# ESP32_Touch_Indoor_Environment_Expansion.net
KiCad netlist of a schematic drawn in EAGLE
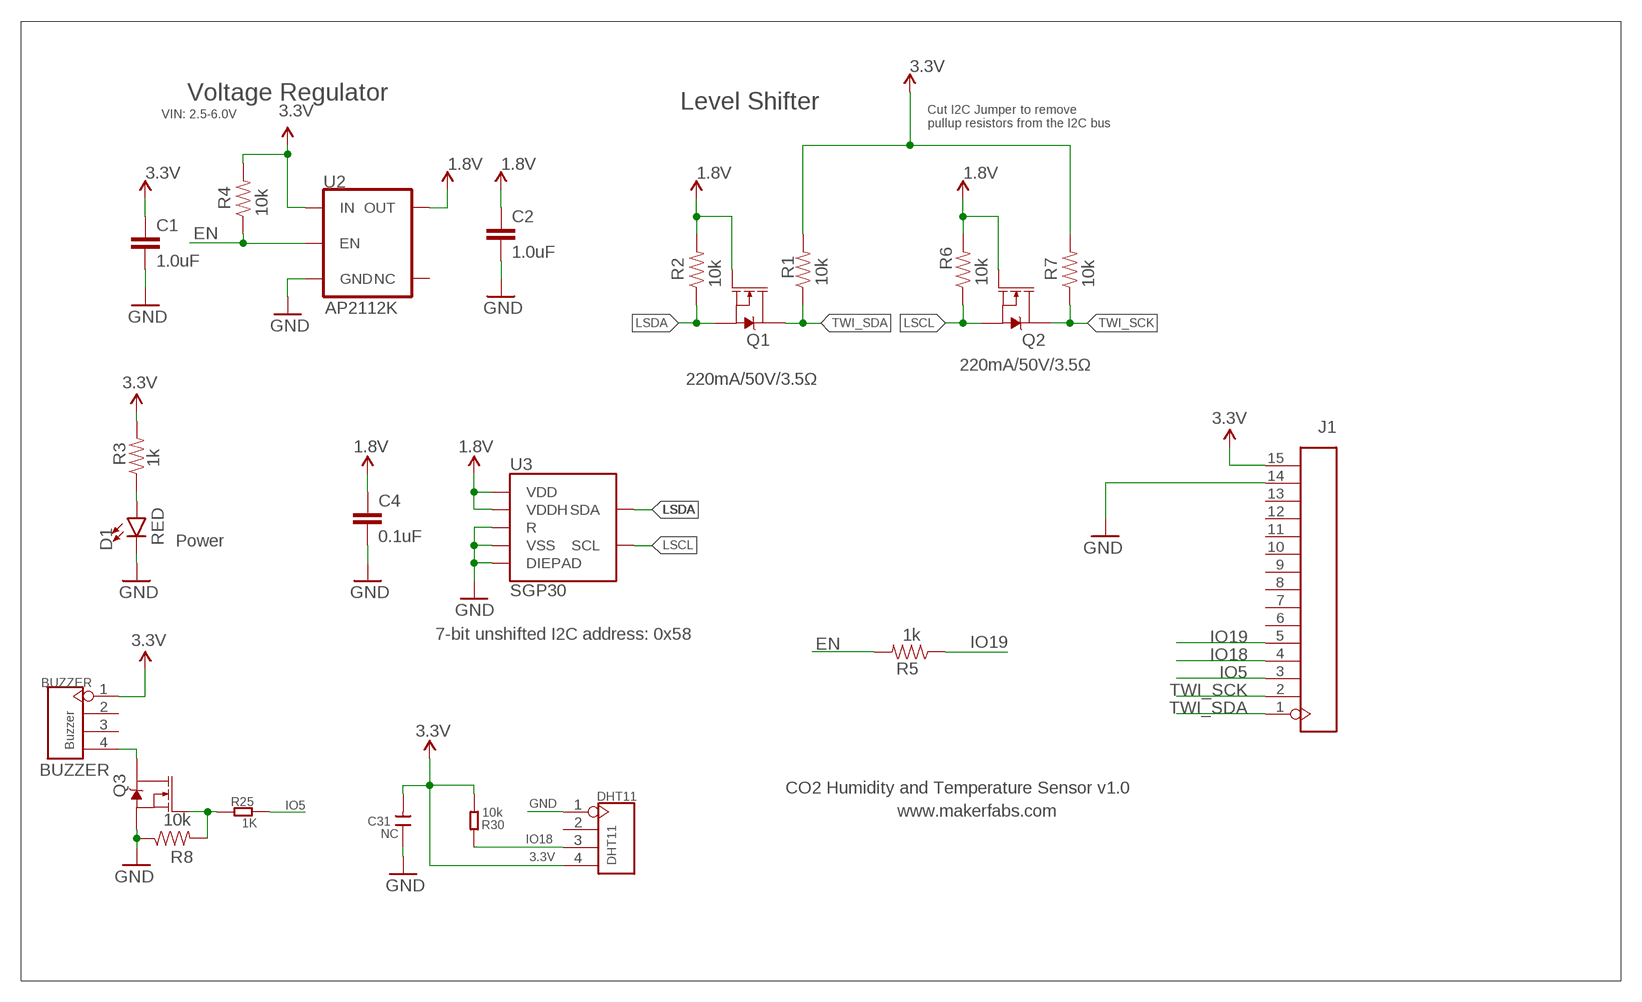
[diagram p0: schematic, sheet 1]

(export (version "E")
  (design (tool "Eeschema 10.0.6"))
  (components
    (comp (ref "BUZZER")
      (value "Buzzer")
      (footprint "eagle-import:4P-65_35ROUND")
      (libsource (lib "eagle-import") (part "HEADER-4P-60/35MILROUND"))
    )
    (comp (ref "C1")
      (value "1.0uF")
      (footprint "eagle-import:0603")
      (libsource (lib "eagle-import") (part "1.0UF-0603-16V-10%"))
    )
    (comp (ref "C2")
      (value "1.0uF")
      (footprint "eagle-import:0603")
      (libsource (lib "eagle-import") (part "1.0UF-0603-16V-10%"))
    )
    (comp (ref "C4")
      (value "0.1uF")
      (footprint "eagle-import:0603")
      (libsource (lib "eagle-import") (part "0.1UF-0603-25V-(+80/-20%)"))
    )
    (comp (ref "C31")
      (value "NC")
      (footprint "eagle-import:0603")
      (libsource (lib "eagle-import") (part "C-0603"))
    )
    (comp (ref "D1")
      (value "RED")
      (footprint "eagle-import:LED-0603")
      (libsource (lib "eagle-import") (part "LED-RED0603"))
    )
    (comp (ref "DHT11")
      (value "DHT11")
      (footprint "eagle-import:4P-65_35ROUND")
      (libsource (lib "eagle-import") (part "HEADER-4P-60/35MILROUND"))
    )
    (comp (ref "J1")
      (value "HEADER-1X15P3")
      (footprint "eagle-import:DIP-1X15-2.54MM-W")
      (libsource (lib "eagle-import") (part "HEADER-1X15P3"))
    )
    (comp (ref "Q1")
      (value "220mA/50V/3.5Ω")
      (footprint "eagle-import:SOT23-3")
      (libsource (lib "eagle-import") (part "MOSFET-NCH-BSS138"))
    )
    (comp (ref "Q2")
      (value "220mA/50V/3.5Ω")
      (footprint "eagle-import:SOT23-3")
      (libsource (lib "eagle-import") (part "MOSFET-NCH-BSS138"))
    )
    (comp (ref "Q3")
      (value "220mA/50V/3.5Ω")
      (footprint "eagle-import:SOT23-3")
      (fields (field (name "PROD_ID") "TRANS-00830"))
      (libsource (lib "eagle-import") (part "MOSFET-NCH-BSS138"))
    )
    (comp (ref "R1")
      (value "10k")
      (footprint "eagle-import:0603")
      (libsource (lib "eagle-import") (part "10KOHM-0603-1/10W-1%"))
    )
    (comp (ref "R2")
      (value "10k")
      (footprint "eagle-import:0603")
      (libsource (lib "eagle-import") (part "10KOHM-0603-1/10W-1%"))
    )
    (comp (ref "R3")
      (value "1k")
      (footprint "eagle-import:0603")
      (libsource (lib "eagle-import") (part "1KOHM-0603-1/10W-1%"))
    )
    (comp (ref "R4")
      (value "10k")
      (footprint "eagle-import:0603")
      (fields (field (name "PROD_ID") "RES-00824"))
      (libsource (lib "eagle-import") (part "10KOHM-0603-1/10W-1%"))
    )
    (comp (ref "R5")
      (value "1k")
      (footprint "eagle-import:0603")
      (fields (field (name "PROD_ID") "RES-07856"))
      (libsource (lib "eagle-import") (part "1KOHM-0603-1/10W-1%"))
    )
    (comp (ref "R6")
      (value "10k")
      (footprint "eagle-import:0603")
      (libsource (lib "eagle-import") (part "10KOHM-0603-1/10W-1%"))
    )
    (comp (ref "R7")
      (value "10k")
      (footprint "eagle-import:0603")
      (libsource (lib "eagle-import") (part "10KOHM-0603-1/10W-1%"))
    )
    (comp (ref "R8")
      (value "10k")
      (footprint "eagle-import:0603")
      (fields (field (name "PROD_ID") "RES-00824"))
      (libsource (lib "eagle-import") (part "10KOHM-0603-1/10W-1%"))
    )
    (comp (ref "R25")
      (value "1K")
      (footprint "eagle-import:R0603")
      (libsource (lib "eagle-import") (part "R-0603"))
    )
    (comp (ref "R30")
      (value "10k")
      (footprint "eagle-import:R0603")
      (libsource (lib "eagle-import") (part "R-0603"))
    )
    (comp (ref "U2")
      (value "AP2112K")
      (footprint "eagle-import:SOT23-5")
      (libsource (lib "eagle-import") (part "V_REG_AP2112K-3.3V"))
    )
    (comp (ref "U3")
      (value "SGP30")
      (footprint "eagle-import:SGP30")
      (libsource (lib "eagle-import") (part "SGP30"))
    )
  )
  (nets
    (net (code "1") (name "/EN") (class "Default")
      (node (ref "R4") (pin "1") (pinfunction "1_1") (pintype "passive"))
      (node (ref "R5") (pin "2") (pinfunction "2_2") (pintype "passive"))
      (node (ref "U2") (pin "3") (pinfunction "EN_3") (pintype "input"))
    )
    (net (code "2") (name "/IO5") (class "Default")
      (node (ref "J1") (pin "3") (pinfunction "3_3") (pintype "bidirectional"))
      (node (ref "R25") (pin "1") (pinfunction "1_1") (pintype "passive"))
    )
    (net (code "3") (name "/IO18") (class "Default")
      (node (ref "DHT11") (pin "3") (pinfunction "P$3_3") (pintype "bidirectional"))
      (node (ref "J1") (pin "4") (pinfunction "4_4") (pintype "bidirectional"))
      (node (ref "R30") (pin "1") (pinfunction "1_1") (pintype "passive"))
    )
    (net (code "4") (name "/IO19") (class "Default")
      (node (ref "J1") (pin "5") (pinfunction "5_5") (pintype "bidirectional"))
      (node (ref "R5") (pin "1") (pinfunction "1_1") (pintype "passive"))
    )
    (net (code "5") (name "1.8V") (class "Default")
      (node (ref "C2") (pin "1") (pinfunction "1_1") (pintype "passive"))
      (node (ref "C4") (pin "1") (pinfunction "1_1") (pintype "passive"))
      (node (ref "Q1") (pin "1") (pinfunction "G_1") (pintype "bidirectional"))
      (node (ref "Q2") (pin "1") (pinfunction "G_1") (pintype "bidirectional"))
      (node (ref "R2") (pin "2") (pinfunction "2_2") (pintype "passive"))
      (node (ref "R6") (pin "2") (pinfunction "2_2") (pintype "passive"))
      (node (ref "U2") (pin "5") (pinfunction "OUT_5") (pintype "passive"))
      (node (ref "U3") (pin "1") (pinfunction "VDD_1") (pintype "bidirectional"))
      (node (ref "U3") (pin "5") (pinfunction "VDDH_5") (pintype "bidirectional"))
    )
    (net (code "6") (name "3.3V") (class "Default")
      (node (ref "BUZZER") (pin "1") (pinfunction "P$1_1") (pintype "bidirectional"))
      (node (ref "C1") (pin "1") (pinfunction "1_1") (pintype "passive"))
      (node (ref "C31") (pin "2") (pinfunction "2_2") (pintype "passive"))
      (node (ref "DHT11") (pin "4") (pinfunction "P$4_4") (pintype "bidirectional"))
      (node (ref "J1") (pin "15") (pinfunction "15_15") (pintype "bidirectional"))
      (node (ref "R1") (pin "2") (pinfunction "2_2") (pintype "passive"))
      (node (ref "R3") (pin "2") (pinfunction "2_2") (pintype "passive"))
      (node (ref "R30") (pin "2") (pinfunction "2_2") (pintype "passive"))
      (node (ref "R4") (pin "2") (pinfunction "2_2") (pintype "passive"))
      (node (ref "R7") (pin "2") (pinfunction "2_2") (pintype "passive"))
      (node (ref "U2") (pin "1") (pinfunction "IN_1") (pintype "input"))
    )
    (net (code "7") (name "GND") (class "Default")
      (node (ref "C1") (pin "2") (pinfunction "2_2") (pintype "passive"))
      (node (ref "C2") (pin "2") (pinfunction "2_2") (pintype "passive"))
      (node (ref "C31") (pin "1") (pinfunction "1_1") (pintype "passive"))
      (node (ref "C4") (pin "2") (pinfunction "2_2") (pintype "passive"))
      (node (ref "D1") (pin "C") (pinfunction "C_C") (pintype "passive"))
      (node (ref "DHT11") (pin "1") (pinfunction "P$1_1") (pintype "bidirectional"))
      (node (ref "J1") (pin "14") (pinfunction "14_14") (pintype "bidirectional"))
      (node (ref "Q3") (pin "2") (pinfunction "S_2") (pintype "bidirectional"))
      (node (ref "R8") (pin "1") (pinfunction "1_1") (pintype "passive"))
      (node (ref "U2") (pin "2") (pinfunction "GND_2") (pintype "input"))
      (node (ref "U3") (pin "2") (pinfunction "VSS_2") (pintype "bidirectional"))
      (node (ref "U3") (pin "4") (pinfunction "R_4") (pintype "bidirectional"))
      (node (ref "U3") (pin "DIEPAD") (pinfunction "DIEPAD_DIEPAD") (pintype "bidirectional"))
    )
    (net (code "8") (name "LSCL") (class "Default")
      (node (ref "Q2") (pin "2") (pinfunction "S_2") (pintype "bidirectional"))
      (node (ref "R6") (pin "1") (pinfunction "1_1") (pintype "passive"))
      (node (ref "U3") (pin "6") (pinfunction "SCL_6") (pintype "bidirectional"))
    )
    (net (code "9") (name "LSDA") (class "Default")
      (node (ref "Q1") (pin "2") (pinfunction "S_2") (pintype "bidirectional"))
      (node (ref "R2") (pin "1") (pinfunction "1_1") (pintype "passive"))
      (node (ref "U3") (pin "3") (pinfunction "SDA_3") (pintype "bidirectional"))
    )
    (net (code "10") (name "Net-(BUZZER-P$4)") (class "Default")
      (node (ref "BUZZER") (pin "4") (pinfunction "P$4_4") (pintype "bidirectional"))
      (node (ref "Q3") (pin "3") (pinfunction "D_3") (pintype "bidirectional"))
    )
    (net (code "11") (name "Net-(D1-PadA)") (class "Default")
      (node (ref "D1") (pin "A") (pinfunction "A_A") (pintype "passive"))
      (node (ref "R3") (pin "1") (pinfunction "1_1") (pintype "passive"))
    )
    (net (code "12") (name "Net-(Q3-G)") (class "Default")
      (node (ref "Q3") (pin "1") (pinfunction "G_1") (pintype "bidirectional"))
      (node (ref "R25") (pin "2") (pinfunction "2_2") (pintype "passive"))
      (node (ref "R8") (pin "2") (pinfunction "2_2") (pintype "passive"))
    )
    (net (code "13") (name "TWI_SCK") (class "Default")
      (node (ref "J1") (pin "2") (pinfunction "2_2") (pintype "bidirectional"))
      (node (ref "Q2") (pin "3") (pinfunction "D_3") (pintype "bidirectional"))
      (node (ref "R7") (pin "1") (pinfunction "1_1") (pintype "passive"))
    )
    (net (code "14") (name "TWI_SDA") (class "Default")
      (node (ref "J1") (pin "1") (pinfunction "1_1") (pintype "bidirectional"))
      (node (ref "Q1") (pin "3") (pinfunction "D_3") (pintype "bidirectional"))
      (node (ref "R1") (pin "1") (pinfunction "1_1") (pintype "passive"))
    )
    (net (code "15") (name "unconnected-(BUZZER-P$2-Pad2)") (class "Default")
      (node (ref "BUZZER") (pin "2") (pinfunction "P$2_2") (pintype "bidirectional"))
    )
    (net (code "16") (name "unconnected-(BUZZER-P$3-Pad3)") (class "Default")
      (node (ref "BUZZER") (pin "3") (pinfunction "P$3_3") (pintype "bidirectional"))
    )
    (net (code "17") (name "unconnected-(DHT11-P$2-Pad2)") (class "Default")
      (node (ref "DHT11") (pin "2") (pinfunction "P$2_2") (pintype "bidirectional"))
    )
    (net (code "18") (name "unconnected-(J1-Pad6)") (class "Default")
      (node (ref "J1") (pin "6") (pinfunction "6_6") (pintype "bidirectional"))
    )
    (net (code "19") (name "unconnected-(J1-Pad7)") (class "Default")
      (node (ref "J1") (pin "7") (pinfunction "7_7") (pintype "bidirectional"))
    )
    (net (code "20") (name "unconnected-(J1-Pad8)") (class "Default")
      (node (ref "J1") (pin "8") (pinfunction "8_8") (pintype "bidirectional"))
    )
    (net (code "21") (name "unconnected-(J1-Pad9)") (class "Default")
      (node (ref "J1") (pin "9") (pinfunction "9_9") (pintype "bidirectional"))
    )
    (net (code "22") (name "unconnected-(J1-Pad10)") (class "Default")
      (node (ref "J1") (pin "10") (pinfunction "10_10") (pintype "bidirectional"))
    )
    (net (code "23") (name "unconnected-(J1-Pad11)") (class "Default")
      (node (ref "J1") (pin "11") (pinfunction "11_11") (pintype "bidirectional"))
    )
    (net (code "24") (name "unconnected-(J1-Pad12)") (class "Default")
      (node (ref "J1") (pin "12") (pinfunction "12_12") (pintype "bidirectional"))
    )
    (net (code "25") (name "unconnected-(J1-Pad13)") (class "Default")
      (node (ref "J1") (pin "13") (pinfunction "13_13") (pintype "bidirectional"))
    )
    (net (code "26") (name "unconnected-(U2-NC-Pad4)") (class "Default")
      (node (ref "U2") (pin "4") (pinfunction "NC_4") (pintype "no_connect"))
    )
  )
)
